# OSP_Carrier_V7_Release_Power.net
KiCad netlist of a schematic drawn in Altium Designer
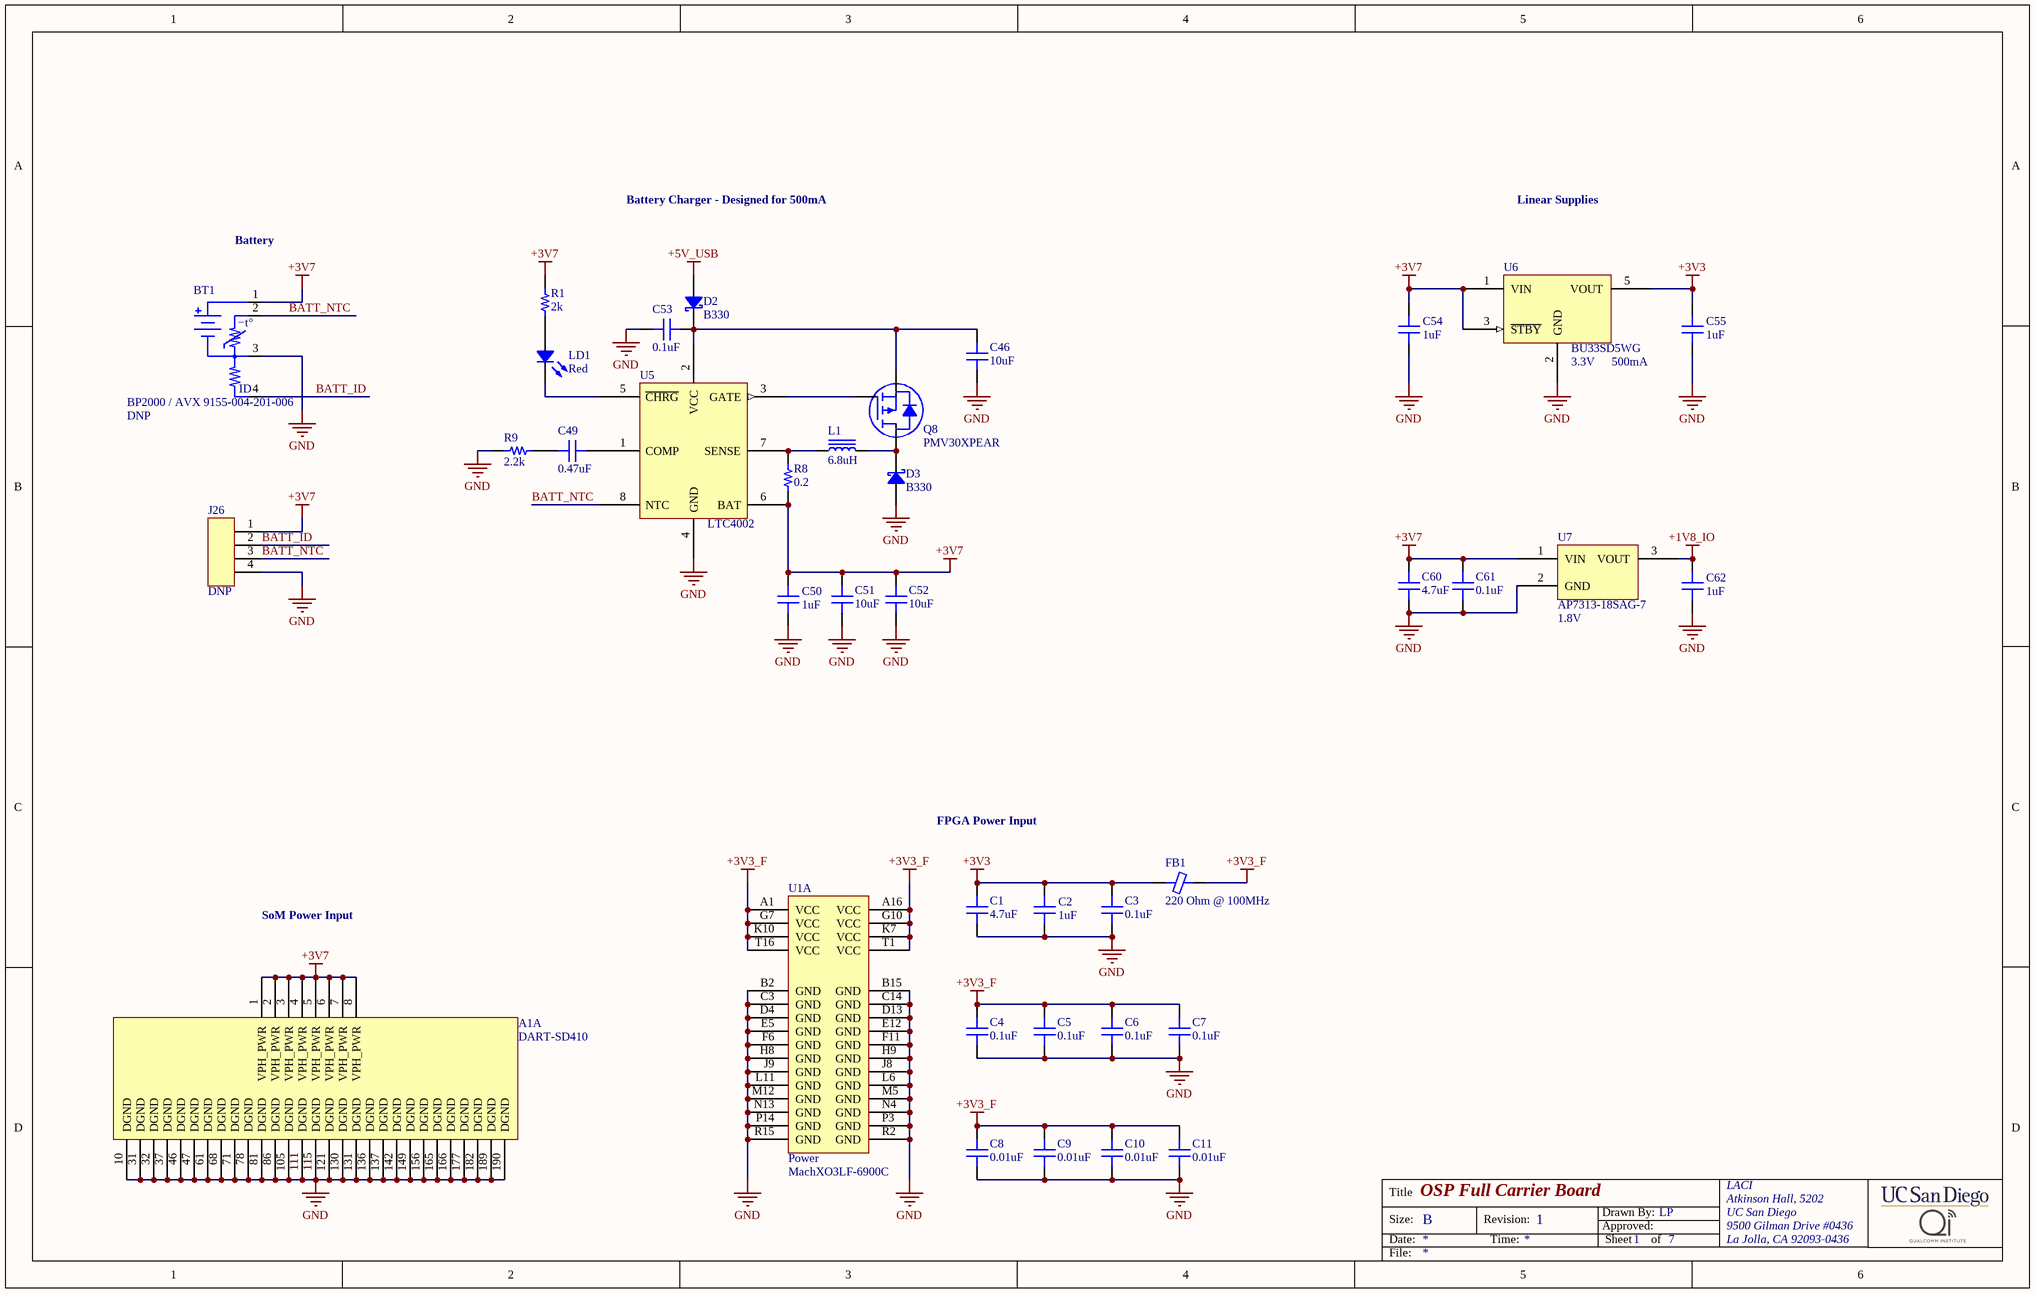
[diagram p0: OSP_Carrier_V7_Release_Power.SchDoc]

(export (version "E")
  (design (tool "Eeschema 10.0.6"))
  (components
    (comp (ref "A1")
      (value "DART-SD410")
      (footprint "DART-SD410")
      (description "Variscite DART-SD410 System on Module")
      (libsource (lib "DART-SD410") (part "DART-SD410"))
    )
    (comp (ref "BT1")
      (value "BP2000 / AVX 9155-004-201-006")
      (footprint "SAMSUNG_BP2000")
      (description "Samsung BP2000 2000mAh battery for Galaxy Camera 2, connector AVX 9155-004-201-006")
      (fields (field (name "DNP") "DNP"))
      (libsource (lib "OSP_Symbols") (part "SAMSUNG_BP2000"))
    )
    (comp (ref "C1")
      (value "4.7uF")
      (footprint "CAP 0402/1005")
      (description "CAP CER 4.7UF 10V X5R 0402")
      (fields
        (field (name "PART NUMBER") "C1005X5R1A475K050BC")
        (field (name "MANUFACTURER") "TDK Corporation")
      )
      (libsource (lib "Celestial Library Database") (part "Capacitor"))
    )
    (comp (ref "C2")
      (value "1uF")
      (footprint "CAP 0402/1005")
      (description "CAP CER 1UF 10V X5R 0402")
      (fields
        (field (name "PART NUMBER") "GRM155R61A105KE15D")
        (field (name "MANUFACTURER") "Murata Electronics North America")
      )
      (libsource (lib "Celestial Library Database") (part "Capacitor"))
    )
    (comp (ref "C3")
      (value "0.1uF")
      (footprint "CAP 0402/1005")
      (description "CAP CER 0.1UF 50V X7R 0402")
      (fields
        (field (name "PART NUMBER") "C1005X7R1H104K050BB")
        (field (name "MANUFACTURER") "TDK Corporation")
      )
      (libsource (lib "Celestial Library Database") (part "Capacitor"))
    )
    (comp (ref "C4")
      (value "0.1uF")
      (footprint "CAP 0402/1005")
      (description "CAP CER 0.1UF 50V X7R 0402")
      (fields
        (field (name "PART NUMBER") "C1005X7R1H104K050BB")
        (field (name "MANUFACTURER") "TDK Corporation")
      )
      (libsource (lib "Celestial Library Database") (part "Capacitor"))
    )
    (comp (ref "C5")
      (value "0.1uF")
      (footprint "CAP 0402/1005")
      (description "CAP CER 0.1UF 50V X7R 0402")
      (fields
        (field (name "PART NUMBER") "C1005X7R1H104K050BB")
        (field (name "MANUFACTURER") "TDK Corporation")
      )
      (libsource (lib "Celestial Library Database") (part "Capacitor"))
    )
    (comp (ref "C6")
      (value "0.1uF")
      (footprint "CAP 0402/1005")
      (description "CAP CER 0.1UF 50V X7R 0402")
      (fields
        (field (name "PART NUMBER") "C1005X7R1H104K050BB")
        (field (name "MANUFACTURER") "TDK Corporation")
      )
      (libsource (lib "Celestial Library Database") (part "Capacitor"))
    )
    (comp (ref "C7")
      (value "0.1uF")
      (footprint "CAP 0402/1005")
      (description "CAP CER 0.1UF 50V X7R 0402")
      (fields
        (field (name "PART NUMBER") "C1005X7R1H104K050BB")
        (field (name "MANUFACTURER") "TDK Corporation")
      )
      (libsource (lib "Celestial Library Database") (part "Capacitor"))
    )
    (comp (ref "C8")
      (value "0.01uF")
      (footprint "CAP 0402/1005")
      (description "CAP CER 10000PF 25V X7R 0402")
      (fields (field (name "PART NUMBER") "CC0402KRX7R8BB103") (field (name "MANUFACTURER") "Yageo"))
      (libsource (lib "Celestial Library Database") (part "Capacitor"))
    )
    (comp (ref "C9")
      (value "0.01uF")
      (footprint "CAP 0402/1005")
      (description "CAP CER 10000PF 25V X7R 0402")
      (fields (field (name "PART NUMBER") "CC0402KRX7R8BB103") (field (name "MANUFACTURER") "Yageo"))
      (libsource (lib "Celestial Library Database") (part "Capacitor"))
    )
    (comp (ref "C10")
      (value "0.01uF")
      (footprint "CAP 0402/1005")
      (description "CAP CER 10000PF 25V X7R 0402")
      (fields (field (name "PART NUMBER") "CC0402KRX7R8BB103") (field (name "MANUFACTURER") "Yageo"))
      (libsource (lib "Celestial Library Database") (part "Capacitor"))
    )
    (comp (ref "C11")
      (value "0.01uF")
      (footprint "CAP 0402/1005")
      (description "CAP CER 10000PF 25V X7R 0402")
      (fields (field (name "PART NUMBER") "CC0402KRX7R8BB103") (field (name "MANUFACTURER") "Yageo"))
      (libsource (lib "Celestial Library Database") (part "Capacitor"))
    )
    (comp (ref "C46")
      (value "10uF")
      (footprint "CAP 1206/3216")
      (description "CAP CER 10UF 25V X7R 1206")
      (fields (field (name "PART NUMBER") "C1206C106M3RACTU") (field (name "MANUFACTURER") "Kemet"))
      (libsource (lib "Celestial Library Database") (part "Capacitor"))
    )
    (comp (ref "C49")
      (value "0.47uF")
      (footprint "CAP 0402/1005")
      (description "CAP CER 0.47UF 10V X5R 0402")
      (fields
        (field (name "PART NUMBER") "GRM155R61A474KE15D")
        (field (name "MANUFACTURER") "Murata Electronics North America")
      )
      (libsource (lib "Celestial Library Database") (part "Capacitor"))
    )
    (comp (ref "C50")
      (value "1uF")
      (footprint "CAP 0402/1005")
      (description "CAP CER 1UF 10V X5R 0402")
      (fields
        (field (name "PART NUMBER") "GRM155R61A105KE15D")
        (field (name "MANUFACTURER") "Murata Electronics North America")
      )
      (libsource (lib "Celestial Library Database") (part "Capacitor"))
    )
    (comp (ref "C51")
      (value "10uF")
      (footprint "CAP 1206/3216")
      (description "CAP CER 10UF 25V X7R 1206")
      (fields (field (name "PART NUMBER") "C1206C106M3RACTU") (field (name "MANUFACTURER") "Kemet"))
      (libsource (lib "Celestial Library Database") (part "Capacitor"))
    )
    (comp (ref "C52")
      (value "10uF")
      (footprint "CAP 1206/3216")
      (description "CAP CER 10UF 25V X7R 1206")
      (fields (field (name "PART NUMBER") "C1206C106M3RACTU") (field (name "MANUFACTURER") "Kemet"))
      (libsource (lib "Celestial Library Database") (part "Capacitor"))
    )
    (comp (ref "C53")
      (value "0.1uF")
      (footprint "CAP 0402/1005")
      (description "CAP CER 0.1UF 50V X7R 0402")
      (fields
        (field (name "PART NUMBER") "C1005X7R1H104K050BB")
        (field (name "MANUFACTURER") "TDK Corporation")
      )
      (libsource (lib "Celestial Library Database") (part "Capacitor"))
    )
    (comp (ref "C54")
      (value "1uF")
      (footprint "CAP 0402/1005")
      (description "CAP CER 1UF 10V X5R 0402")
      (fields
        (field (name "PART NUMBER") "GRM155R61A105KE15D")
        (field (name "MANUFACTURER") "Murata Electronics North America")
      )
      (libsource (lib "Celestial Library Database") (part "Capacitor"))
    )
    (comp (ref "C55")
      (value "1uF")
      (footprint "CAP 0402/1005")
      (description "CAP CER 1UF 10V X5R 0402")
      (fields
        (field (name "PART NUMBER") "GRM155R61A105KE15D")
        (field (name "MANUFACTURER") "Murata Electronics North America")
      )
      (libsource (lib "Celestial Library Database") (part "Capacitor"))
    )
    (comp (ref "C60")
      (value "4.7uF")
      (footprint "CAP 0402/1005")
      (description "CAP CER 4.7UF 10V X5R 0402")
      (fields
        (field (name "PART NUMBER") "C1005X5R1A475K050BC")
        (field (name "MANUFACTURER") "TDK Corporation")
      )
      (libsource (lib "Celestial Library Database") (part "Capacitor"))
    )
    (comp (ref "C61")
      (value "0.1uF")
      (footprint "CAP 0402/1005")
      (description "CAP CER 0.1UF 50V X7R 0402")
      (fields
        (field (name "PART NUMBER") "C1005X7R1H104K050BB")
        (field (name "MANUFACTURER") "TDK Corporation")
      )
      (libsource (lib "Celestial Library Database") (part "Capacitor"))
    )
    (comp (ref "C62")
      (value "1uF")
      (footprint "CAP 0402/1005")
      (description "CAP CER 1UF 10V X5R 0402")
      (fields
        (field (name "PART NUMBER") "GRM155R61A105KE15D")
        (field (name "MANUFACTURER") "Murata Electronics North America")
      )
      (libsource (lib "Celestial Library Database") (part "Capacitor"))
    )
    (comp (ref "D2")
      (value "B330")
      (footprint "DO214AC SMA")
      (description "B330AE-13 Schottky Diode 3A 30V")
      (libsource (lib "OSP_Symbols") (part "B330A"))
    )
    (comp (ref "D3")
      (value "B330")
      (footprint "DO214AC SMA")
      (description "B330AE-13 Schottky Diode 3A 30V")
      (libsource (lib "OSP_Symbols") (part "B330A"))
    )
    (comp (ref "FB1")
      (value "220 Ohm @ 100MHz")
      (footprint "FER 0402/1005")
      (description "FERRITE CHIP 220 OHM 500MA 0402")
      (fields
        (field (name "PART NUMBER") "CIM05U221NC")
        (field (name "MANUFACTURER") "Samsung Electro-Mechanics America, Inc.")
      )
      (libsource (lib "Celestial Library Database") (part "Ferrite Chip"))
    )
    (comp (ref "J26")
      (value "Shallow")
      (footprint "AMPHENOL_10125839-04RAEHLF_DNP")
      (description "Amphenol 10125839-04RAEHLF (Do Not Populate)")
      (fields (field (name "DNP") "DNP"))
      (libsource (lib "OSP_Symbols") (part "AMPHENOL_10125839-04RAEHLF_DNP"))
    )
    (comp (ref "L1")
      (value "6.8uH")
      (footprint "LAIRD_TYS6028")
      (description "Laird TYS60286R8M-10 6.8uH 2.4A 47mOhms")
      (libsource (lib "OSP_Symbols") (part "Laird_TYS60286R8M-10"))
    )
    (comp (ref "LD1")
      (value "Red")
      (footprint "LED 0603/1608 RED")
      (description "LED RED CLEAR 0603 SMD")
      (fields (field (name "PART NUMBER") "LTST-C191KRKT") (field (name "MANUFACTURER") "Lite-On Inc."))
      (libsource (lib "Celestial Library Database") (part "LED"))
    )
    (comp (ref "Q8")
      (value "PMV30XPEAR")
      (footprint "NXP_SOT23")
      (description "PMV30XPEAR PMOS 20V -5.3A 28mOhms")
      (libsource (lib "OSP_Symbols") (part "NXP_PMV30XPEAR"))
    )
    (comp (ref "R1")
      (value "2k")
      (footprint "RES 0402/1005")
      (description "RES SMD 2K OHM 1% 1/10W 0402")
      (fields
        (field (name "PART NUMBER") "ERJ-2RKF2001X")
        (field (name "MANUFACTURER") "Panasonic Electronic Components")
      )
      (libsource (lib "Celestial Library Database") (part "Resistor"))
    )
    (comp (ref "R8")
      (value "0.2")
      (footprint "STACKPOLE CSR1206")
      (description "RES SMD 0.2 OHM 1% 1/2W 1206")
      (fields
        (field (name "PART NUMBER") "CSR1206FKR200")
        (field (name "MANUFACTURER") "Stackpole Electronics Inc.")
      )
      (libsource (lib "Celestial Library Database") (part "Resistor"))
    )
    (comp (ref "R9")
      (value "2.2k")
      (footprint "RES 0402/1005")
      (description "RES SMD 2.2K OHM 1% 1/10W 0402")
      (fields
        (field (name "PART NUMBER") "ERJ-2RKF2201X")
        (field (name "MANUFACTURER") "Panasonic Electronic Components")
      )
      (libsource (lib "Celestial Library Database") (part "Resistor"))
    )
    (comp (ref "U1")
      (value "MachXO3LF-6900C")
      (footprint "LCMXO3_caBGA_BG256")
      (description "Lattice MachXO3LF-6900C-5BG256C FPGA")
      (libsource (lib "OSP_Symbols") (part "LCMXO3LF-6900C-XBG256X"))
    )
    (comp (ref "U5")
      (value "LTC4002")
      (footprint "AD_LT_S8")
      (description "Analog / Linear 1.5A Single Cell Li-Ion Battery Charger")
      (libsource (lib "OSP_Symbols") (part "LTC4002"))
    )
    (comp (ref "U6")
      (value "BU33SD5WG")
      (footprint "ROHM_SSOP5")
      (description "ROHM BU33SD5WG-TR 3.3V 500mA LDO")
      (fields (field (name "VOLTAGE") "3.3V") (field (name "CURRENT") "500mA"))
      (libsource (lib "OSP_Symbols") (part "ROHM_BU33SD5WG"))
    )
    (comp (ref "U7")
      (value "AP7313-18SAG-7")
      (footprint "DIODES SOT-23-3")
      (description "IC REG LDO 1.8V 0.15A SOT23-3")
      (fields (field (name "MANUFACTURER") "Diodes Incorporated") (field (name "VOLTAGE - OUTPUT") "1.8V"))
      (libsource (lib "Celestial Library Database") (part "Diodes Inc AP7313"))
    )
  )
  (nets
    (net (code "1") (name "+1V8_IO") (class "Default")
      (node (ref "C62") (pin "1") (pinfunction "1_1") (pintype "passive"))
      (node (ref "U7") (pin "3") (pinfunction "VOUT_3") (pintype "passive"))
    )
    (net (code "2") (name "+3V3") (class "Default")
      (node (ref "C1") (pin "2") (pinfunction "2_2") (pintype "passive"))
      (node (ref "C2") (pin "1") (pinfunction "1_1") (pintype "passive"))
      (node (ref "C3") (pin "2") (pinfunction "2_2") (pintype "passive"))
      (node (ref "C55") (pin "1") (pinfunction "1_1") (pintype "passive"))
      (node (ref "FB1") (pin "1") (pinfunction "1_1") (pintype "passive"))
      (node (ref "U6") (pin "5") (pinfunction "VOUT_5") (pintype "power_in"))
    )
    (net (code "3") (name "+3V3_F") (class "Default")
      (node (ref "C10") (pin "2") (pinfunction "2_2") (pintype "passive"))
      (node (ref "C11") (pin "2") (pinfunction "2_2") (pintype "passive"))
      (node (ref "C4") (pin "2") (pinfunction "2_2") (pintype "passive"))
      (node (ref "C5") (pin "2") (pinfunction "2_2") (pintype "passive"))
      (node (ref "C6") (pin "2") (pinfunction "2_2") (pintype "passive"))
      (node (ref "C7") (pin "2") (pinfunction "2_2") (pintype "passive"))
      (node (ref "C8") (pin "2") (pinfunction "2_2") (pintype "passive"))
      (node (ref "C9") (pin "2") (pinfunction "2_2") (pintype "passive"))
      (node (ref "FB1") (pin "2") (pinfunction "2_2") (pintype "passive"))
      (node (ref "U1") (pin "A1") (pinfunction "VCC_A1") (pintype "power_in"))
      (node (ref "U1") (pin "A16") (pinfunction "VCC_A16") (pintype "power_in"))
      (node (ref "U1") (pin "G10") (pinfunction "VCC_G10") (pintype "power_in"))
      (node (ref "U1") (pin "G7") (pinfunction "VCC_G7") (pintype "power_in"))
      (node (ref "U1") (pin "K10") (pinfunction "VCC_K10") (pintype "power_in"))
      (node (ref "U1") (pin "K7") (pinfunction "VCC_K7") (pintype "power_in"))
      (node (ref "U1") (pin "T1") (pinfunction "VCC_T1") (pintype "power_in"))
      (node (ref "U1") (pin "T16") (pinfunction "VCC_T16") (pintype "power_in"))
    )
    (net (code "4") (name "+3V7") (class "Default")
      (node (ref "A1") (pin "1") (pinfunction "VPH_PWR_1") (pintype "power_in"))
      (node (ref "A1") (pin "2") (pinfunction "VPH_PWR_2") (pintype "power_in"))
      (node (ref "A1") (pin "3") (pinfunction "VPH_PWR_3") (pintype "power_in"))
      (node (ref "A1") (pin "4") (pinfunction "VPH_PWR_4") (pintype "power_in"))
      (node (ref "A1") (pin "5") (pinfunction "VPH_PWR_5") (pintype "power_in"))
      (node (ref "A1") (pin "6") (pinfunction "VPH_PWR_6") (pintype "power_in"))
      (node (ref "A1") (pin "7") (pinfunction "VPH_PWR_7") (pintype "power_in"))
      (node (ref "A1") (pin "8") (pinfunction "VPH_PWR_8") (pintype "power_in"))
      (node (ref "BT1") (pin "1") (pinfunction "+_1") (pintype "power_in"))
      (node (ref "C50") (pin "1") (pinfunction "1_1") (pintype "passive"))
      (node (ref "C51") (pin "1") (pinfunction "1_1") (pintype "passive"))
      (node (ref "C52") (pin "1") (pinfunction "1_1") (pintype "passive"))
      (node (ref "C54") (pin "1") (pinfunction "1_1") (pintype "passive"))
      (node (ref "C60") (pin "2") (pinfunction "2_2") (pintype "passive"))
      (node (ref "C61") (pin "2") (pinfunction "2_2") (pintype "passive"))
      (node (ref "J26") (pin "1") (pintype "passive"))
      (node (ref "R1") (pin "2") (pinfunction "2_2") (pintype "passive"))
      (node (ref "R8") (pin "1") (pinfunction "1_1") (pintype "passive"))
      (node (ref "U5") (pin "6") (pinfunction "BAT_6") (pintype "passive"))
      (node (ref "U6") (pin "1") (pinfunction "VIN_1") (pintype "power_in"))
      (node (ref "U6") (pin "3") (pinfunction "~{STBY}_3") (pintype "input"))
      (node (ref "U7") (pin "1") (pinfunction "VIN_1") (pintype "passive"))
    )
    (net (code "5") (name "+5V_USB") (class "Default")
      (node (ref "D2") (pin "1") (pinfunction "1_1") (pintype "passive"))
    )
    (net (code "6") (name "/BATT_ID") (class "Default")
      (node (ref "BT1") (pin "4") (pinfunction "ID_4") (pintype "passive"))
      (node (ref "J26") (pin "2") (pintype "passive"))
    )
    (net (code "7") (name "/BATT_NTC") (class "Default")
      (node (ref "BT1") (pin "2") (pinfunction "NTC_2") (pintype "passive"))
      (node (ref "J26") (pin "3") (pintype "passive"))
      (node (ref "U5") (pin "8") (pinfunction "NTC_8") (pintype "passive"))
    )
    (net (code "8") (name "GND") (class "Default")
      (node (ref "A1") (pin "10") (pinfunction "DGND_10") (pintype "power_in"))
      (node (ref "A1") (pin "105") (pinfunction "DGND_105") (pintype "power_in"))
      (node (ref "A1") (pin "111") (pinfunction "DGND_111") (pintype "power_in"))
      (node (ref "A1") (pin "115") (pinfunction "DGND_115") (pintype "power_in"))
      (node (ref "A1") (pin "121") (pinfunction "DGND_121") (pintype "power_in"))
      (node (ref "A1") (pin "130") (pinfunction "DGND_130") (pintype "power_in"))
      (node (ref "A1") (pin "131") (pinfunction "DGND_131") (pintype "power_in"))
      (node (ref "A1") (pin "136") (pinfunction "DGND_136") (pintype "power_in"))
      (node (ref "A1") (pin "137") (pinfunction "DGND_137") (pintype "power_in"))
      (node (ref "A1") (pin "142") (pinfunction "DGND_142") (pintype "power_in"))
      (node (ref "A1") (pin "149") (pinfunction "DGND_149") (pintype "power_in"))
      (node (ref "A1") (pin "156") (pinfunction "DGND_156") (pintype "power_in"))
      (node (ref "A1") (pin "165") (pinfunction "DGND_165") (pintype "power_in"))
      (node (ref "A1") (pin "166") (pinfunction "DGND_166") (pintype "power_in"))
      (node (ref "A1") (pin "177") (pinfunction "DGND_177") (pintype "power_in"))
      (node (ref "A1") (pin "182") (pinfunction "DGND_182") (pintype "power_in"))
      (node (ref "A1") (pin "189") (pinfunction "DGND_189") (pintype "power_in"))
      (node (ref "A1") (pin "190") (pinfunction "DGND_190") (pintype "power_in"))
      (node (ref "A1") (pin "31") (pinfunction "DGND_31") (pintype "power_in"))
      (node (ref "A1") (pin "32") (pinfunction "DGND_32") (pintype "power_in"))
      (node (ref "A1") (pin "37") (pinfunction "DGND_37") (pintype "power_in"))
      (node (ref "A1") (pin "46") (pinfunction "DGND_46") (pintype "power_in"))
      (node (ref "A1") (pin "47") (pinfunction "DGND_47") (pintype "power_in"))
      (node (ref "A1") (pin "61") (pinfunction "DGND_61") (pintype "power_in"))
      (node (ref "A1") (pin "68") (pinfunction "DGND_68") (pintype "power_in"))
      (node (ref "A1") (pin "71") (pinfunction "DGND_71") (pintype "power_in"))
      (node (ref "A1") (pin "78") (pinfunction "DGND_78") (pintype "power_in"))
      (node (ref "A1") (pin "81") (pinfunction "DGND_81") (pintype "power_in"))
      (node (ref "A1") (pin "86") (pinfunction "DGND_86") (pintype "power_in"))
      (node (ref "BT1") (pin "3") (pinfunction "−_3") (pintype "power_in"))
      (node (ref "C1") (pin "1") (pinfunction "1_1") (pintype "passive"))
      (node (ref "C10") (pin "1") (pinfunction "1_1") (pintype "passive"))
      (node (ref "C11") (pin "1") (pinfunction "1_1") (pintype "passive"))
      (node (ref "C2") (pin "2") (pinfunction "2_2") (pintype "passive"))
      (node (ref "C3") (pin "1") (pinfunction "1_1") (pintype "passive"))
      (node (ref "C4") (pin "1") (pinfunction "1_1") (pintype "passive"))
      (node (ref "C46") (pin "2") (pinfunction "2_2") (pintype "passive"))
      (node (ref "C5") (pin "1") (pinfunction "1_1") (pintype "passive"))
      (node (ref "C50") (pin "2") (pinfunction "2_2") (pintype "passive"))
      (node (ref "C51") (pin "2") (pinfunction "2_2") (pintype "passive"))
      (node (ref "C52") (pin "2") (pinfunction "2_2") (pintype "passive"))
      (node (ref "C53") (pin "2") (pinfunction "2_2") (pintype "passive"))
      (node (ref "C54") (pin "2") (pinfunction "2_2") (pintype "passive"))
      (node (ref "C55") (pin "2") (pinfunction "2_2") (pintype "passive"))
      (node (ref "C6") (pin "1") (pinfunction "1_1") (pintype "passive"))
      (node (ref "C60") (pin "1") (pinfunction "1_1") (pintype "passive"))
      (node (ref "C61") (pin "1") (pinfunction "1_1") (pintype "passive"))
      (node (ref "C62") (pin "2") (pinfunction "2_2") (pintype "passive"))
      (node (ref "C7") (pin "1") (pinfunction "1_1") (pintype "passive"))
      (node (ref "C8") (pin "1") (pinfunction "1_1") (pintype "passive"))
      (node (ref "C9") (pin "1") (pinfunction "1_1") (pintype "passive"))
      (node (ref "D3") (pin "1") (pinfunction "1_1") (pintype "passive"))
      (node (ref "J26") (pin "4") (pintype "passive"))
      (node (ref "R9") (pin "2") (pinfunction "2_2") (pintype "passive"))
      (node (ref "U1") (pin "B15") (pinfunction "GND_B15") (pintype "power_in"))
      (node (ref "U1") (pin "B2") (pinfunction "GND_B2") (pintype "power_in"))
      (node (ref "U1") (pin "C14") (pinfunction "GND_C14") (pintype "power_in"))
      (node (ref "U1") (pin "C3") (pinfunction "GND_C3") (pintype "power_in"))
      (node (ref "U1") (pin "D13") (pinfunction "GND_D13") (pintype "power_in"))
      (node (ref "U1") (pin "D4") (pinfunction "GND_D4") (pintype "power_in"))
      (node (ref "U1") (pin "E12") (pinfunction "GND_E12") (pintype "power_in"))
      (node (ref "U1") (pin "E5") (pinfunction "GND_E5") (pintype "power_in"))
      (node (ref "U1") (pin "F11") (pinfunction "GND_F11") (pintype "power_in"))
      (node (ref "U1") (pin "F6") (pinfunction "GND_F6") (pintype "power_in"))
      (node (ref "U1") (pin "H8") (pinfunction "GND_H8") (pintype "power_in"))
      (node (ref "U1") (pin "H9") (pinfunction "GND_H9") (pintype "power_in"))
      (node (ref "U1") (pin "J8") (pinfunction "GND_J8") (pintype "power_in"))
      (node (ref "U1") (pin "J9") (pinfunction "GND_J9") (pintype "power_in"))
      (node (ref "U1") (pin "L11") (pinfunction "GND_L11") (pintype "power_in"))
      (node (ref "U1") (pin "L6") (pinfunction "GND_L6") (pintype "power_in"))
      (node (ref "U1") (pin "M12") (pinfunction "GND_M12") (pintype "power_in"))
      (node (ref "U1") (pin "M5") (pinfunction "GND_M5") (pintype "power_in"))
      (node (ref "U1") (pin "N13") (pinfunction "GND_N13") (pintype "power_in"))
      (node (ref "U1") (pin "N4") (pinfunction "GND_N4") (pintype "power_in"))
      (node (ref "U1") (pin "P14") (pinfunction "GND_P14") (pintype "power_in"))
      (node (ref "U1") (pin "P3") (pinfunction "GND_P3") (pintype "power_in"))
      (node (ref "U1") (pin "R15") (pinfunction "GND_R15") (pintype "power_in"))
      (node (ref "U1") (pin "R2") (pinfunction "GND_R2") (pintype "power_in"))
      (node (ref "U5") (pin "4") (pinfunction "GND_4") (pintype "power_in"))
      (node (ref "U6") (pin "2") (pinfunction "GND_2") (pintype "power_in"))
      (node (ref "U7") (pin "2") (pinfunction "GND_2") (pintype "passive"))
    )
    (net (code "9") (name "Net-(C49-Pad2)") (class "Default")
      (node (ref "C49") (pin "2") (pinfunction "2_2") (pintype "passive"))
      (node (ref "R9") (pin "1") (pinfunction "1_1") (pintype "passive"))
    )
    (net (code "10") (name "Net-(LD1-Pad1)") (class "Default")
      (node (ref "LD1") (pin "1") (pinfunction "1_1") (pintype "passive"))
      (node (ref "R1") (pin "1") (pinfunction "1_1") (pintype "passive"))
    )
    (net (code "11") (name "Net-(Q8-D)") (class "Default")
      (node (ref "D3") (pin "2") (pinfunction "2_2") (pintype "passive"))
      (node (ref "L1") (pin "2") (pinfunction "2_2") (pintype "passive"))
      (node (ref "Q8") (pin "3") (pinfunction "D_3") (pintype "passive"))
    )
    (net (code "12") (name "Net-(Q8-G)") (class "Default")
      (node (ref "Q8") (pin "1") (pinfunction "G_1") (pintype "passive"))
      (node (ref "U5") (pin "3") (pinfunction "GATE_3") (pintype "output"))
    )
    (net (code "13") (name "Net-(Q8-S)") (class "Default")
      (node (ref "C46") (pin "1") (pinfunction "1_1") (pintype "passive"))
      (node (ref "C53") (pin "1") (pinfunction "1_1") (pintype "passive"))
      (node (ref "D2") (pin "2") (pinfunction "2_2") (pintype "passive"))
      (node (ref "Q8") (pin "2") (pinfunction "S_2") (pintype "passive"))
      (node (ref "U5") (pin "2") (pinfunction "VCC_2") (pintype "power_in"))
    )
    (net (code "14") (name "Net-(U5-COMP)") (class "Default")
      (node (ref "C49") (pin "1") (pinfunction "1_1") (pintype "passive"))
      (node (ref "U5") (pin "1") (pinfunction "COMP_1") (pintype "passive"))
    )
    (net (code "15") (name "Net-(U5-SENSE)") (class "Default")
      (node (ref "L1") (pin "1") (pinfunction "1_1") (pintype "passive"))
      (node (ref "R8") (pin "2") (pinfunction "2_2") (pintype "passive"))
      (node (ref "U5") (pin "7") (pinfunction "SENSE_7") (pintype "passive"))
    )
    (net (code "16") (name "Net-(U5-~{CHRG})") (class "Default")
      (node (ref "LD1") (pin "2") (pinfunction "2_2") (pintype "passive"))
      (node (ref "U5") (pin "5") (pinfunction "~{CHRG}_5") (pintype "open_collector"))
    )
  )
)
